# 06_LEDs.net
KiCad netlist of a schematic drawn in Altium Designer
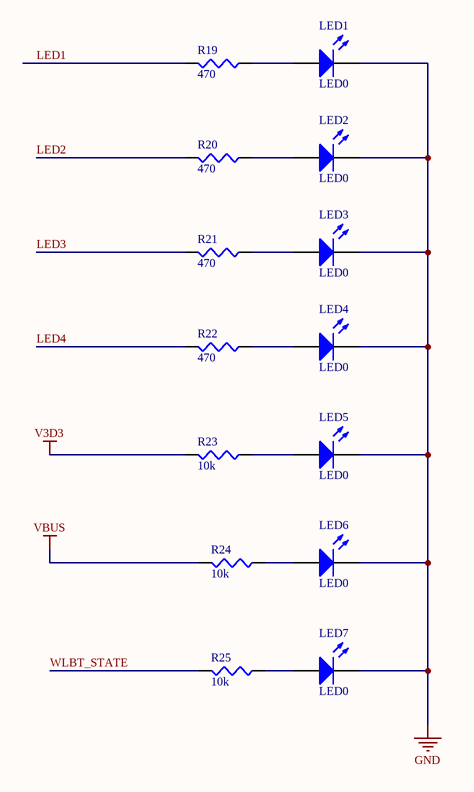
[diagram p0: 06_LEDs.SchDoc]

(export (version "E")
  (design (tool "Eeschema 10.0.6"))
  (components
    (comp (ref "LED1")
      (value "LED0")
      (footprint "J1-0603")
      (description "Typical INFRARED GaAs LED")
      (fields (field (name "PUBLISHER") "Altium Limited"))
      (libsource (lib "Miscellaneous Devices") (part "LED0"))
    )
    (comp (ref "LED2")
      (value "LED0")
      (footprint "J1-0603")
      (description "Typical INFRARED GaAs LED")
      (fields (field (name "PUBLISHER") "Altium Limited"))
      (libsource (lib "Miscellaneous Devices") (part "LED0"))
    )
    (comp (ref "LED3")
      (value "LED0")
      (footprint "J1-0603")
      (description "Typical INFRARED GaAs LED")
      (fields (field (name "PUBLISHER") "Altium Limited"))
      (libsource (lib "Miscellaneous Devices") (part "LED0"))
    )
    (comp (ref "LED4")
      (value "LED0")
      (footprint "J1-0603")
      (description "Typical INFRARED GaAs LED")
      (fields (field (name "PUBLISHER") "Altium Limited"))
      (libsource (lib "Miscellaneous Devices") (part "LED0"))
    )
    (comp (ref "LED5")
      (value "LED0")
      (footprint "J1-0603")
      (description "Typical INFRARED GaAs LED")
      (fields (field (name "PUBLISHER") "Altium Limited"))
      (libsource (lib "Miscellaneous Devices") (part "LED0"))
    )
    (comp (ref "LED6")
      (value "LED0")
      (footprint "J1-0603")
      (description "Typical INFRARED GaAs LED")
      (fields (field (name "PUBLISHER") "Altium Limited"))
      (libsource (lib "Miscellaneous Devices") (part "LED0"))
    )
    (comp (ref "LED7")
      (value "LED0")
      (footprint "J1-0603")
      (description "Typical INFRARED GaAs LED")
      (fields (field (name "PUBLISHER") "Altium Limited"))
      (libsource (lib "Miscellaneous Devices") (part "LED0"))
    )
    (comp (ref "R19")
      (value "470")
      (footprint "0402")
      (description "Resistor")
      (fields (field (name "Comment") "Res3") (field (name "PUBLISHER") "Altium Limited"))
      (libsource (lib "Miscellaneous Devices") (part "Res3"))
    )
    (comp (ref "R20")
      (value "470")
      (footprint "0402")
      (description "Resistor")
      (fields (field (name "Comment") "Res3") (field (name "PUBLISHER") "Altium Limited"))
      (libsource (lib "Miscellaneous Devices") (part "Res3"))
    )
    (comp (ref "R21")
      (value "470")
      (footprint "0402")
      (description "Resistor")
      (fields (field (name "Comment") "Res3") (field (name "PUBLISHER") "Altium Limited"))
      (libsource (lib "Miscellaneous Devices") (part "Res3"))
    )
    (comp (ref "R22")
      (value "470")
      (footprint "0402")
      (description "Resistor")
      (fields (field (name "Comment") "Res3") (field (name "PUBLISHER") "Altium Limited"))
      (libsource (lib "Miscellaneous Devices") (part "Res3"))
    )
    (comp (ref "R23")
      (value "10k")
      (footprint "0402")
      (description "Resistor")
      (fields (field (name "Comment") "Res3") (field (name "PUBLISHER") "Altium Limited"))
      (libsource (lib "Miscellaneous Devices") (part "Res3"))
    )
    (comp (ref "R24")
      (value "10k")
      (footprint "0402")
      (description "Resistor")
      (fields (field (name "Comment") "Res3") (field (name "PUBLISHER") "Altium Limited"))
      (libsource (lib "Miscellaneous Devices") (part "Res3"))
    )
    (comp (ref "R25")
      (value "10k")
      (footprint "0402")
      (description "Resistor")
      (fields (field (name "Comment") "Res3") (field (name "PUBLISHER") "Altium Limited"))
      (libsource (lib "Miscellaneous Devices") (part "Res3"))
    )
  )
  (nets
    (net (code "1") (name "/LED1") (class "Default")
      (node (ref "R19") (pin "2") (pinfunction "2_2") (pintype "passive"))
    )
    (net (code "2") (name "/LED2") (class "Default")
      (node (ref "R20") (pin "2") (pinfunction "2_2") (pintype "passive"))
    )
    (net (code "3") (name "/LED3") (class "Default")
      (node (ref "R21") (pin "2") (pinfunction "2_2") (pintype "passive"))
    )
    (net (code "4") (name "/LED4") (class "Default")
      (node (ref "R22") (pin "2") (pinfunction "2_2") (pintype "passive"))
    )
    (net (code "5") (name "/WLBT_STATE") (class "Default")
      (node (ref "R25") (pin "2") (pinfunction "2_2") (pintype "passive"))
    )
    (net (code "6") (name "GND") (class "Default")
      (node (ref "LED1") (pin "2") (pinfunction "K_2") (pintype "passive"))
      (node (ref "LED2") (pin "2") (pinfunction "K_2") (pintype "passive"))
      (node (ref "LED3") (pin "2") (pinfunction "K_2") (pintype "passive"))
      (node (ref "LED4") (pin "2") (pinfunction "K_2") (pintype "passive"))
      (node (ref "LED5") (pin "2") (pinfunction "K_2") (pintype "passive"))
      (node (ref "LED6") (pin "2") (pinfunction "K_2") (pintype "passive"))
      (node (ref "LED7") (pin "2") (pinfunction "K_2") (pintype "passive"))
    )
    (net (code "7") (name "Net-(LED1-A)") (class "Default")
      (node (ref "LED1") (pin "1") (pinfunction "A_1") (pintype "passive"))
      (node (ref "R19") (pin "1") (pinfunction "1_1") (pintype "passive"))
    )
    (net (code "8") (name "Net-(LED2-A)") (class "Default")
      (node (ref "LED2") (pin "1") (pinfunction "A_1") (pintype "passive"))
      (node (ref "R20") (pin "1") (pinfunction "1_1") (pintype "passive"))
    )
    (net (code "9") (name "Net-(LED3-A)") (class "Default")
      (node (ref "LED3") (pin "1") (pinfunction "A_1") (pintype "passive"))
      (node (ref "R21") (pin "1") (pinfunction "1_1") (pintype "passive"))
    )
    (net (code "10") (name "Net-(LED4-A)") (class "Default")
      (node (ref "LED4") (pin "1") (pinfunction "A_1") (pintype "passive"))
      (node (ref "R22") (pin "1") (pinfunction "1_1") (pintype "passive"))
    )
    (net (code "11") (name "Net-(LED5-A)") (class "Default")
      (node (ref "LED5") (pin "1") (pinfunction "A_1") (pintype "passive"))
      (node (ref "R23") (pin "1") (pinfunction "1_1") (pintype "passive"))
    )
    (net (code "12") (name "Net-(LED6-A)") (class "Default")
      (node (ref "LED6") (pin "1") (pinfunction "A_1") (pintype "passive"))
      (node (ref "R24") (pin "1") (pinfunction "1_1") (pintype "passive"))
    )
    (net (code "13") (name "Net-(LED7-A)") (class "Default")
      (node (ref "LED7") (pin "1") (pinfunction "A_1") (pintype "passive"))
      (node (ref "R25") (pin "1") (pinfunction "1_1") (pintype "passive"))
    )
    (net (code "14") (name "V3D3") (class "Default")
      (node (ref "R23") (pin "2") (pinfunction "2_2") (pintype "passive"))
    )
    (net (code "15") (name "VBUS") (class "Default")
      (node (ref "R24") (pin "2") (pinfunction "2_2") (pintype "passive"))
    )
  )
)
